# Thermokoppel.net
KiCad netlist of a schematic drawn in Altium Designer
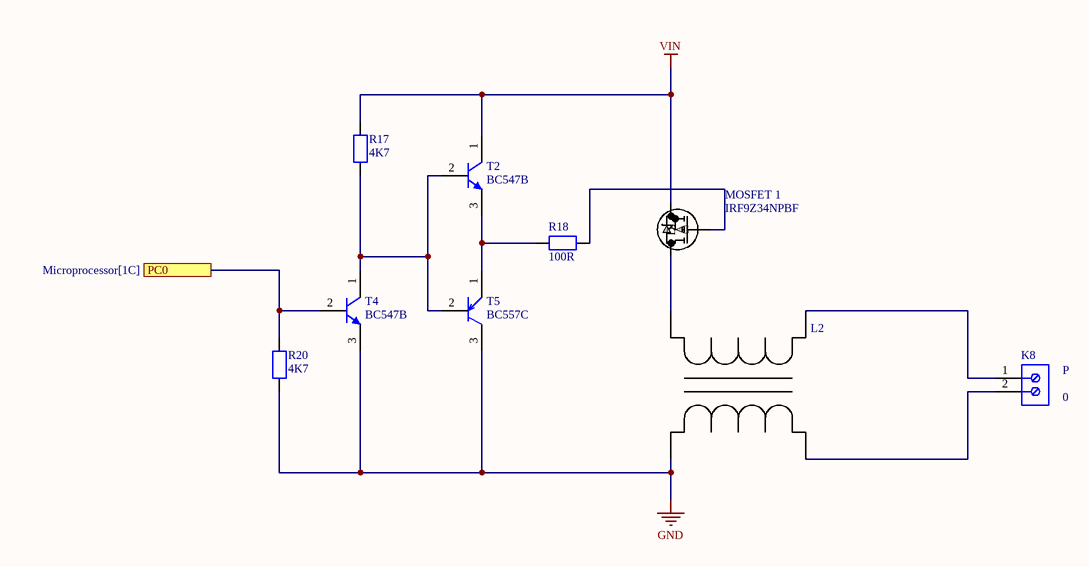
[diagram p0: Thermokoppel.SchDoc]

(export (version "E")
  (design (tool "Eeschema 10.0.6"))
  (components
    (comp (ref "K8")
      (value "~")
      (footprint "2pin connector")
      (description "PC Terminal Block, Pitch 6.35 mm, 1 x 2 Position, Height 21.5 mm, Tail Lenght 5.1 mm, RoHS, Bulk")
      (fields (field (name "MANUFACTURER") "Phoenix Contact"))
      (libsource (lib "soldeerstation") (part "Printkroonsteen 2pin"))
    )
    (comp (ref "L2")
      (value "~")
      (footprint "spoel2")
      (description "No Description Available")
      (fields
        (field (name "MANUFACTURER_PART_NUMBER") "CM2545X171B-10")
        (field (name "COPYRIGHT") "Copyright (C) 2023 Ultra Librarian. All rights reserved.")
      )
      (libsource (lib "soldeerstation") (part "Spoel2"))
    )
    (comp (ref "MOSFET 1")
      (value "IRF9Z34NPBF")
      (footprint "IRF")
      (description "No Description Available")
      (fields (field (name "COPYRIGHT") "Copyright (C) 2023 Ultra Librarian. All rights reserved."))
      (libsource (lib "soldeerstation") (part "IRF9Z34NPBF"))
    )
    (comp (ref "R17")
      (value "4K7")
      (footprint "Weerstand 1M ohm")
      (fields (field (name "MANUFACTURER") "Vishay Dale") (field (name "PART NUMBER") "CRCW08054K70JNEB"))
      (libsource (lib "soldeerstation") (part "Weerstand 4K7 ohm"))
    )
    (comp (ref "R18")
      (value "100R")
      (footprint "Weerstand 1M ohm")
      (fields (field (name "MANUFACTURER") "Vishay Dale") (field (name "PART NUMBER") "CRCW0805100RFKEA"))
      (libsource (lib "soldeerstation") (part "Weerstand 100 ohm"))
    )
    (comp (ref "R20")
      (value "4K7")
      (footprint "Weerstand 1M ohm")
      (fields (field (name "MANUFACTURER") "Vishay Dale") (field (name "PART NUMBER") "CRCW08054K70JNEB"))
      (libsource (lib "soldeerstation") (part "Weerstand 4K7 ohm"))
    )
    (comp (ref "T2")
      (value "BC547B")
      (footprint "sot23")
      (description "Amplifier Transistor, NPN Silicon, 3-Pin TO-92, Bulk Box")
      (fields (field (name "MANUFACTURER") "On Semiconductor"))
      (libsource (lib "soldeerstation") (part "sot23 (bc547)"))
    )
    (comp (ref "T4")
      (value "BC547B")
      (footprint "sot23")
      (description "Amplifier Transistor, NPN Silicon, 3-Pin TO-92, Bulk Box")
      (fields (field (name "MANUFACTURER") "On Semiconductor"))
      (libsource (lib "soldeerstation") (part "sot23 (bc547)"))
    )
    (comp (ref "T5")
      (value "BC557C")
      (footprint "BC557C")
      (description "Amplifier Transistor, PNP Silicon, 3-Pin TO-92, Bulk Box")
      (fields (field (name "MANUFACTURER") "On Semiconductor"))
      (libsource (lib "soldeerstation") (part "BC557C"))
    )
  )
  (nets
    (net (code "1") (name "/PC0") (class "Default")
      (node (ref "R20") (pin "2") (pinfunction "2_2") (pintype "passive"))
      (node (ref "T4") (pin "2") (pinfunction "B_2") (pintype "passive"))
    )
    (net (code "2") (name "GND") (class "Default")
      (node (ref "L2") (pin "2") (pinfunction "2_2") (pintype "passive"))
      (node (ref "R20") (pin "1") (pinfunction "1_1") (pintype "passive"))
      (node (ref "T4") (pin "3") (pinfunction "E_3") (pintype "passive"))
      (node (ref "T5") (pin "3") (pinfunction "E_3") (pintype "passive"))
    )
    (net (code "3") (name "Net-(K8-Pad1)") (class "Default")
      (node (ref "K8") (pin "1") (pinfunction "1_1") (pintype "passive"))
      (node (ref "L2") (pin "3") (pinfunction "3_3") (pintype "passive"))
    )
    (net (code "4") (name "Net-(K8-Pad2)") (class "Default")
      (node (ref "K8") (pin "2") (pinfunction "2_2") (pintype "passive"))
      (node (ref "L2") (pin "4") (pinfunction "4_4") (pintype "passive"))
    )
    (net (code "5") (name "Net-(MOSFET 1-D)") (class "Default")
      (node (ref "L2") (pin "1") (pinfunction "1_1") (pintype "passive"))
      (node (ref "MOSFET 1") (pin "2") (pinfunction "D_2") (pintype "passive"))
    )
    (net (code "6") (name "Net-(MOSFET 1-G)") (class "Default")
      (node (ref "MOSFET 1") (pin "1") (pinfunction "G_1") (pintype "passive"))
      (node (ref "R18") (pin "2") (pinfunction "2_2") (pintype "passive"))
    )
    (net (code "7") (name "Net-(T2-B)") (class "Default")
      (node (ref "R17") (pin "1") (pinfunction "1_1") (pintype "passive"))
      (node (ref "T2") (pin "2") (pinfunction "B_2") (pintype "passive"))
      (node (ref "T4") (pin "1") (pinfunction "C_1") (pintype "passive"))
      (node (ref "T5") (pin "2") (pinfunction "B_2") (pintype "passive"))
    )
    (net (code "8") (name "Net-(T2-E)") (class "Default")
      (node (ref "R18") (pin "1") (pinfunction "1_1") (pintype "passive"))
      (node (ref "T2") (pin "3") (pinfunction "E_3") (pintype "passive"))
      (node (ref "T5") (pin "1") (pinfunction "C_1") (pintype "passive"))
    )
    (net (code "9") (name "VIN") (class "Default")
      (node (ref "MOSFET 1") (pin "3") (pinfunction "S_3") (pintype "passive"))
      (node (ref "R17") (pin "2") (pinfunction "2_2") (pintype "passive"))
      (node (ref "T2") (pin "1") (pinfunction "C_1") (pintype "passive"))
    )
  )
)
